# main.net
KiCad netlist of a schematic drawn in EAGLE
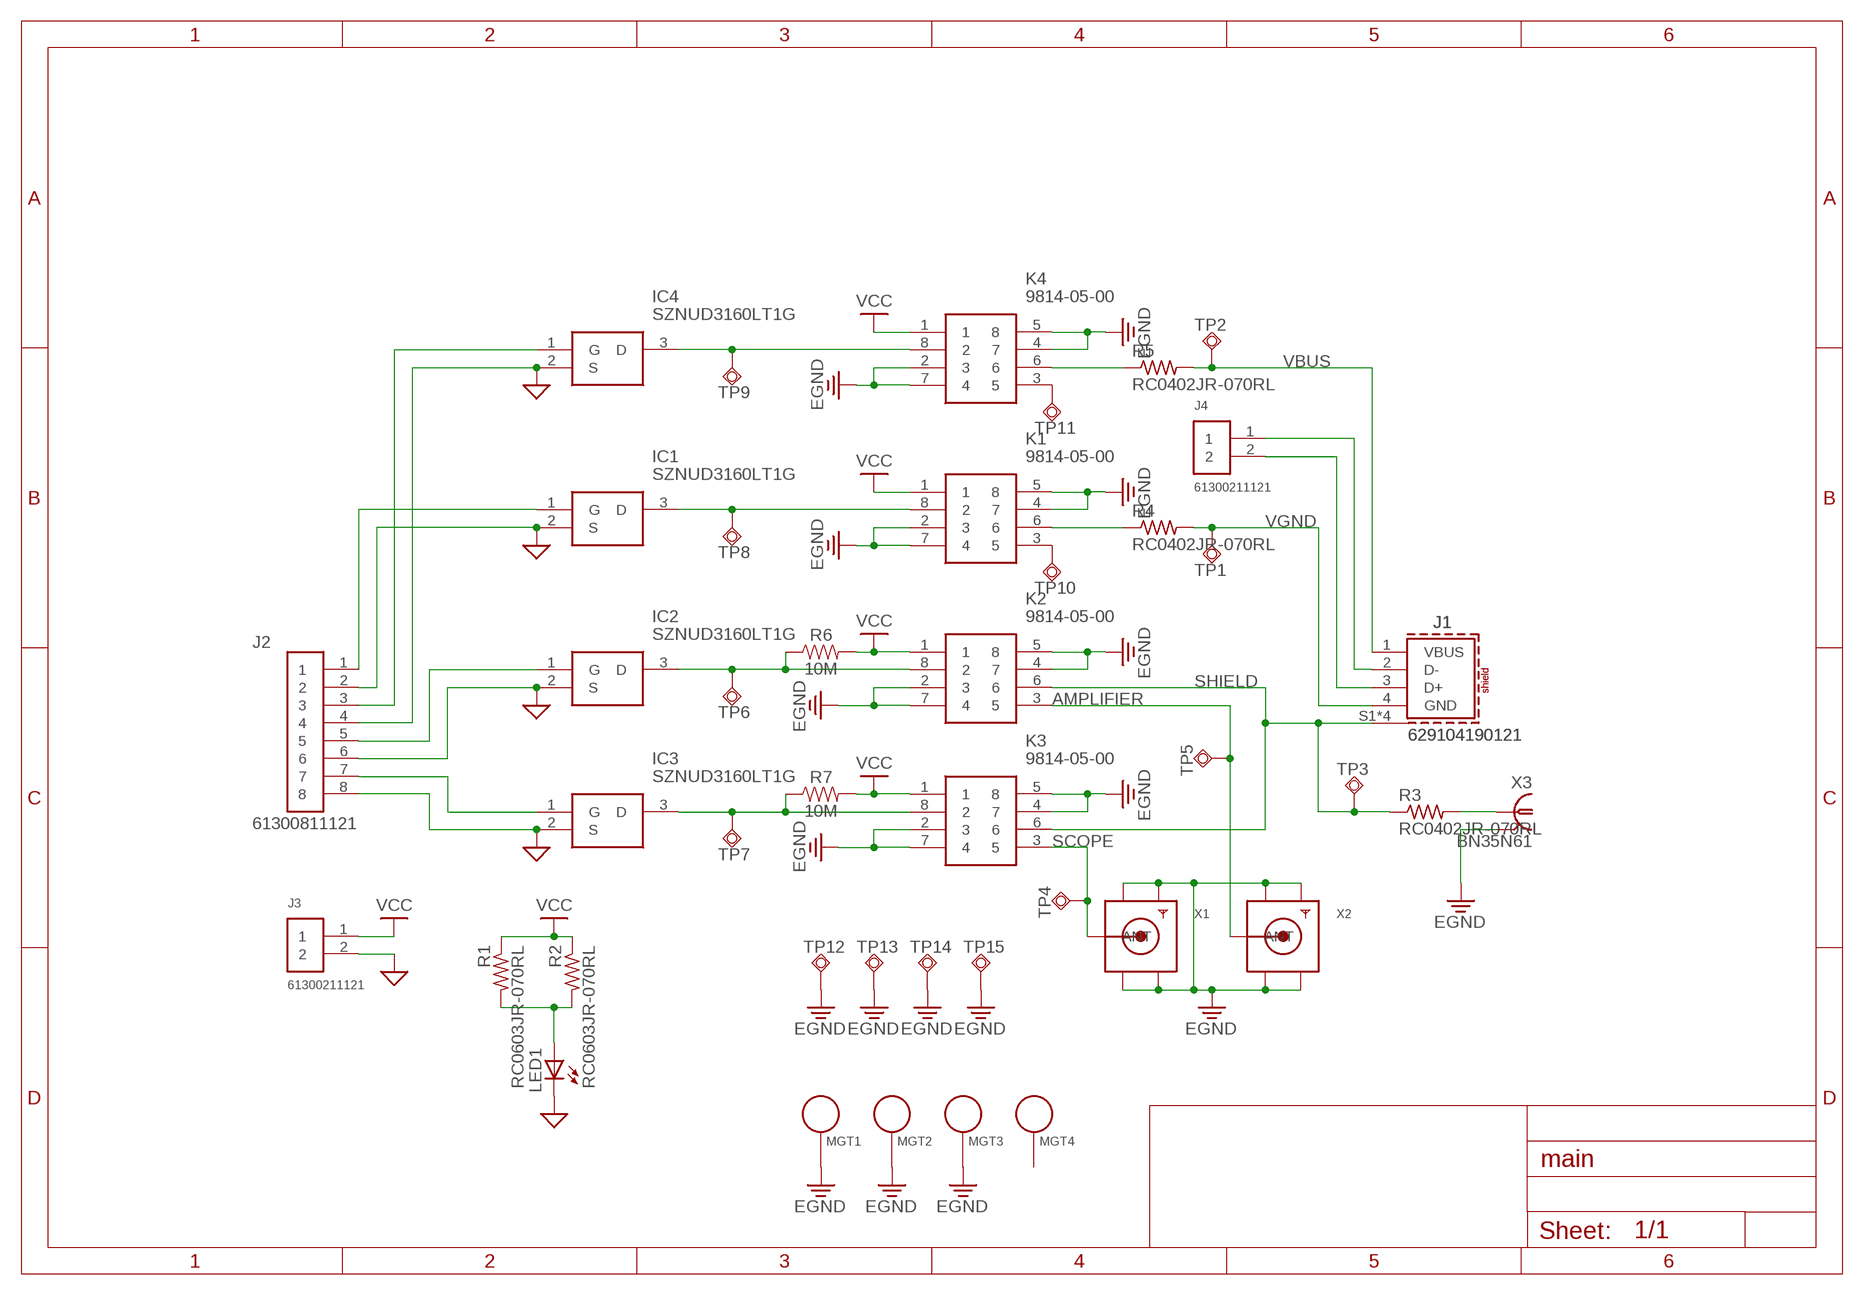
[diagram p0: schematic, sheet 1]

(export (version "E")
  (design (tool "Eeschema 10.0.6"))
  (components
    (comp (ref "IC1")
      (value "SZNUD3160LT1G")
      (footprint "eagle-import:SOT96P237X111-3N")
      (fields (field (name "MOUSER_PART_NUMBER") "863-SZNUD3160LT1G"))
      (libsource (lib "eagle-import") (part "SZNUD3160LT1G"))
    )
    (comp (ref "IC2")
      (value "SZNUD3160LT1G")
      (footprint "eagle-import:SOT96P237X111-3N")
      (fields (field (name "MOUSER_PART_NUMBER") "863-SZNUD3160LT1G"))
      (libsource (lib "eagle-import") (part "SZNUD3160LT1G"))
    )
    (comp (ref "IC3")
      (value "SZNUD3160LT1G")
      (footprint "eagle-import:SOT96P237X111-3N")
      (fields (field (name "MOUSER_PART_NUMBER") "863-SZNUD3160LT1G"))
      (libsource (lib "eagle-import") (part "SZNUD3160LT1G"))
    )
    (comp (ref "IC4")
      (value "SZNUD3160LT1G")
      (footprint "eagle-import:SOT96P237X111-3N")
      (fields (field (name "MOUSER_PART_NUMBER") "863-SZNUD3160LT1G"))
      (libsource (lib "eagle-import") (part "SZNUD3160LT1G"))
    )
    (comp (ref "J1")
      (value "629104190121")
      (footprint "eagle-import:629104190121")
      (libsource (lib "eagle-import") (part "629104190121"))
    )
    (comp (ref "J2")
      (value "61300811121")
      (footprint "eagle-import:61300811121")
      (fields
        (field (name "DIGI_KEY_PART_NUMBER") "732-5321-ND")
        (field (name "MANUFACTURER") "Wurth Electronics Inc.")
        (field (name "CREATED_BY") "PCBLayout.com")
      )
      (libsource (lib "eagle-import") (part "61300811121"))
    )
    (comp (ref "J3")
      (value "61300211121")
      (footprint "eagle-import:61300211121")
      (fields
        (field (name "DIGI_KEY_PART_NUMBER") "732-5315-ND")
        (field (name "MANUFACTURER") "Wurth Electronics Inc.")
        (field (name "CREATED_BY") "PCBLayout.com")
      )
      (libsource (lib "eagle-import") (part "61300211121"))
    )
    (comp (ref "J4")
      (value "61300211121")
      (footprint "eagle-import:61300211121")
      (fields
        (field (name "DIGI_KEY_PART_NUMBER") "732-5315-ND")
        (field (name "MANUFACTURER") "Wurth Electronics Inc.")
        (field (name "CREATED_BY") "PCBLayout.com")
      )
      (libsource (lib "eagle-import") (part "61300211121"))
    )
    (comp (ref "K1")
      (value "9814-05-00")
      (footprint "eagle-import:SOP102P1295X457-8N")
      (fields (field (name "MOUSER_PART_NUMBER") "816-9814-05-00"))
      (libsource (lib "eagle-import") (part "9814-05-00"))
    )
    (comp (ref "K2")
      (value "9814-05-00")
      (footprint "eagle-import:SOP102P1295X457-8N")
      (fields (field (name "MOUSER_PART_NUMBER") "816-9814-05-00"))
      (libsource (lib "eagle-import") (part "9814-05-00"))
    )
    (comp (ref "K3")
      (value "9814-05-00")
      (footprint "eagle-import:SOP102P1295X457-8N")
      (fields (field (name "MOUSER_PART_NUMBER") "816-9814-05-00"))
      (libsource (lib "eagle-import") (part "9814-05-00"))
    )
    (comp (ref "K4")
      (value "9814-05-00")
      (footprint "eagle-import:SOP102P1295X457-8N")
      (fields (field (name "MOUSER_PART_NUMBER") "816-9814-05-00"))
      (libsource (lib "eagle-import") (part "9814-05-00"))
    )
    (comp (ref "LED1")
      (value "LEDCHIPLED_0603")
      (footprint "eagle-import:CHIPLED_0603")
      (libsource (lib "eagle-import") (part "LEDCHIPLED_0603"))
    )
    (comp (ref "MGT1")
      (value "BEAGLEBONEBLACK_MOUNTING_HOLE")
      (footprint "eagle-import:BEAGLEBONEBLACK_MOUNTING_HOLE")
      (libsource (lib "eagle-import") (part "BEAGLEBONEBLACK_MOUNTING_HOLE"))
    )
    (comp (ref "MGT2")
      (value "BEAGLEBONEBLACK_MOUNTING_HOLE")
      (footprint "eagle-import:BEAGLEBONEBLACK_MOUNTING_HOLE")
      (libsource (lib "eagle-import") (part "BEAGLEBONEBLACK_MOUNTING_HOLE"))
    )
    (comp (ref "MGT3")
      (value "BEAGLEBONEBLACK_MOUNTING_HOLE")
      (footprint "eagle-import:BEAGLEBONEBLACK_MOUNTING_HOLE")
      (libsource (lib "eagle-import") (part "BEAGLEBONEBLACK_MOUNTING_HOLE"))
    )
    (comp (ref "MGT4")
      (value "BEAGLEBONEBLACK_MOUNTING_HOLE")
      (footprint "eagle-import:BEAGLEBONEBLACK_MOUNTING_HOLE")
      (libsource (lib "eagle-import") (part "BEAGLEBONEBLACK_MOUNTING_HOLE"))
    )
    (comp (ref "R1")
      (value "RC0603JR-070RL")
      (footprint "eagle-import:RES_0603")
      (fields
        (field (name "DIGIKEY_PART_NUMBER") "311-0.0GRTR-ND")
        (field (name "MANUFACTURER") "Yageo")
        (field (name "CREATED_BY") "PCBLayout.com")
      )
      (libsource (lib "eagle-import") (part "RC0603JR-070RL"))
    )
    (comp (ref "R2")
      (value "RC0603JR-070RL")
      (footprint "eagle-import:RES_0603")
      (fields
        (field (name "DIGIKEY_PART_NUMBER") "311-0.0GRTR-ND")
        (field (name "MANUFACTURER") "Yageo")
        (field (name "CREATED_BY") "PCBLayout.com")
      )
      (libsource (lib "eagle-import") (part "RC0603JR-070RL"))
    )
    (comp (ref "R3")
      (value "RC0402JR-070RL")
      (footprint "eagle-import:RES_0402")
      (fields
        (field (name "DIGIKEY_PART_NUMBER") "311-0.0JRTR-ND")
        (field (name "MANUFACTURER") "Yageo")
        (field (name "CREATED_BY") "PCBLayout.com")
      )
      (libsource (lib "eagle-import") (part "RC0402JR-070RL"))
    )
    (comp (ref "R4")
      (value "RC0402JR-070RL")
      (footprint "eagle-import:RES_0402")
      (fields
        (field (name "DIGIKEY_PART_NUMBER") "311-0.0JRTR-ND")
        (field (name "MANUFACTURER") "Yageo")
        (field (name "CREATED_BY") "PCBLayout.com")
      )
      (libsource (lib "eagle-import") (part "RC0402JR-070RL"))
    )
    (comp (ref "R5")
      (value "RC0402JR-070RL")
      (footprint "eagle-import:RES_0402")
      (fields
        (field (name "DIGIKEY_PART_NUMBER") "311-0.0JRTR-ND")
        (field (name "MANUFACTURER") "Yageo")
        (field (name "CREATED_BY") "PCBLayout.com")
      )
      (libsource (lib "eagle-import") (part "RC0402JR-070RL"))
    )
    (comp (ref "R6")
      (value "10M")
      (footprint "eagle-import:AXIAL-0.3")
      (libsource (lib "eagle-import") (part "10MOHM-HORIZ-1/4W-5%"))
    )
    (comp (ref "R7")
      (value "10M")
      (footprint "eagle-import:AXIAL-0.3")
      (libsource (lib "eagle-import") (part "10MOHM-HORIZ-1/4W-5%"))
    )
    (comp (ref "TP1")
      (value "TESTPAD_TPSQPAD1-13")
      (footprint "eagle-import:TESTPAD_P1-13")
      (libsource (lib "eagle-import") (part "TESTPAD_TPSQPAD1-13"))
    )
    (comp (ref "TP2")
      (value "TESTPAD_TPSQPAD1-13")
      (footprint "eagle-import:TESTPAD_P1-13")
      (libsource (lib "eagle-import") (part "TESTPAD_TPSQPAD1-13"))
    )
    (comp (ref "TP3")
      (value "TESTPAD_TPSQPAD1-13")
      (footprint "eagle-import:TESTPAD_P1-13")
      (libsource (lib "eagle-import") (part "TESTPAD_TPSQPAD1-13"))
    )
    (comp (ref "TP4")
      (value "TESTPAD_TPSQPAD1-13")
      (footprint "eagle-import:TESTPAD_P1-13")
      (libsource (lib "eagle-import") (part "TESTPAD_TPSQPAD1-13"))
    )
    (comp (ref "TP5")
      (value "TESTPAD_TPSQPAD1-13")
      (footprint "eagle-import:TESTPAD_P1-13")
      (libsource (lib "eagle-import") (part "TESTPAD_TPSQPAD1-13"))
    )
    (comp (ref "TP6")
      (value "TESTPAD_TPSQTP07SQ")
      (footprint "eagle-import:TESTPAD_TP07SQ")
      (libsource (lib "eagle-import") (part "TESTPAD_TPSQTP07SQ"))
    )
    (comp (ref "TP7")
      (value "TESTPAD_TPSQTP07SQ")
      (footprint "eagle-import:TESTPAD_TP07SQ")
      (libsource (lib "eagle-import") (part "TESTPAD_TPSQTP07SQ"))
    )
    (comp (ref "TP8")
      (value "TESTPAD_TPSQTP07SQ")
      (footprint "eagle-import:TESTPAD_TP07SQ")
      (libsource (lib "eagle-import") (part "TESTPAD_TPSQTP07SQ"))
    )
    (comp (ref "TP9")
      (value "TESTPAD_TPSQTP07SQ")
      (footprint "eagle-import:TESTPAD_TP07SQ")
      (libsource (lib "eagle-import") (part "TESTPAD_TPSQTP07SQ"))
    )
    (comp (ref "TP10")
      (value "TESTPAD_TPSQPAD1-13")
      (footprint "eagle-import:TESTPAD_P1-13")
      (libsource (lib "eagle-import") (part "TESTPAD_TPSQPAD1-13"))
    )
    (comp (ref "TP11")
      (value "TESTPAD_TPSQPAD1-13")
      (footprint "eagle-import:TESTPAD_P1-13")
      (libsource (lib "eagle-import") (part "TESTPAD_TPSQPAD1-13"))
    )
    (comp (ref "TP12")
      (value "TESTPAD_TPSQPAD1-13")
      (footprint "eagle-import:TESTPAD_P1-13")
      (libsource (lib "eagle-import") (part "TESTPAD_TPSQPAD1-13"))
    )
    (comp (ref "TP13")
      (value "TESTPAD_TPSQPAD1-13")
      (footprint "eagle-import:TESTPAD_P1-13")
      (libsource (lib "eagle-import") (part "TESTPAD_TPSQPAD1-13"))
    )
    (comp (ref "TP14")
      (value "TESTPAD_TPSQPAD1-13")
      (footprint "eagle-import:TESTPAD_P1-13")
      (libsource (lib "eagle-import") (part "TESTPAD_TPSQPAD1-13"))
    )
    (comp (ref "TP15")
      (value "TESTPAD_TPSQPAD1-13")
      (footprint "eagle-import:TESTPAD_P1-13")
      (libsource (lib "eagle-import") (part "TESTPAD_TPSQPAD1-13"))
    )
    (comp (ref "X1")
      (value "SMACONNECTOR_EDGE")
      (footprint "eagle-import:SMA_EDGELAUNCH")
      (libsource (lib "eagle-import") (part "SMACONNECTOR_EDGE"))
    )
    (comp (ref "X2")
      (value "SMACONNECTOR_EDGE")
      (footprint "eagle-import:SMA_EDGELAUNCH")
      (libsource (lib "eagle-import") (part "SMACONNECTOR_EDGE"))
    )
    (comp (ref "X3")
      (value "BN35N61")
      (footprint "eagle-import:B35N61")
      (libsource (lib "eagle-import") (part "BN35N61"))
    )
  )
  (nets
    (net (code "1") (name "/AMPLIFIER") (class "Default")
      (node (ref "K2") (pin "3") (pinfunction "5_3") (pintype "bidirectional"))
      (node (ref "TP5") (pin "TP") (pinfunction "TP_TP") (pintype "input"))
      (node (ref "X2") (pin "P") (pinfunction "ANT_P") (pintype "bidirectional"))
    )
    (net (code "2") (name "/SCOPE") (class "Default")
      (node (ref "K3") (pin "3") (pinfunction "5_3") (pintype "bidirectional"))
      (node (ref "TP4") (pin "TP") (pinfunction "TP_TP") (pintype "input"))
      (node (ref "X1") (pin "P") (pinfunction "ANT_P") (pintype "bidirectional"))
    )
    (net (code "3") (name "/SHIELD") (class "Default")
      (node (ref "J1") (pin "S1") (pinfunction "SHIELD_S1") (pintype "passive"))
      (node (ref "J1") (pin "S2") (pinfunction "SHIELD_S2") (pintype "passive"))
      (node (ref "J1") (pin "S3") (pinfunction "SHIELD_S3") (pintype "passive"))
      (node (ref "J1") (pin "S4") (pinfunction "SHIELD_S4") (pintype "passive"))
      (node (ref "K2") (pin "6") (pinfunction "6_6") (pintype "bidirectional"))
      (node (ref "K3") (pin "6") (pinfunction "6_6") (pintype "bidirectional"))
      (node (ref "R3") (pin "1") (pinfunction "1_1") (pintype "passive"))
      (node (ref "TP3") (pin "TP") (pinfunction "TP_TP") (pintype "input"))
    )
    (net (code "4") (name "/VBUS") (class "Default")
      (node (ref "J1") (pin "1") (pinfunction "VBUS_1") (pintype "passive"))
      (node (ref "R5") (pin "2") (pinfunction "2_2") (pintype "passive"))
      (node (ref "TP2") (pin "TP") (pinfunction "TP_TP") (pintype "input"))
    )
    (net (code "5") (name "/VGND") (class "Default")
      (node (ref "J1") (pin "4") (pinfunction "GND_4") (pintype "passive"))
      (node (ref "R4") (pin "2") (pinfunction "2_2") (pintype "passive"))
      (node (ref "TP1") (pin "TP") (pinfunction "TP_TP") (pintype "input"))
    )
    (net (code "6") (name "EGND") (class "Default")
      (node (ref "K1") (pin "2") (pinfunction "3_2") (pintype "bidirectional"))
      (node (ref "K1") (pin "4") (pinfunction "7_4") (pintype "bidirectional"))
      (node (ref "K1") (pin "5") (pinfunction "8_5") (pintype "bidirectional"))
      (node (ref "K1") (pin "7") (pinfunction "4_7") (pintype "bidirectional"))
      (node (ref "K2") (pin "2") (pinfunction "3_2") (pintype "bidirectional"))
      (node (ref "K2") (pin "4") (pinfunction "7_4") (pintype "bidirectional"))
      (node (ref "K2") (pin "5") (pinfunction "8_5") (pintype "bidirectional"))
      (node (ref "K2") (pin "7") (pinfunction "4_7") (pintype "bidirectional"))
      (node (ref "K3") (pin "2") (pinfunction "3_2") (pintype "bidirectional"))
      (node (ref "K3") (pin "4") (pinfunction "7_4") (pintype "bidirectional"))
      (node (ref "K3") (pin "5") (pinfunction "8_5") (pintype "bidirectional"))
      (node (ref "K3") (pin "7") (pinfunction "4_7") (pintype "bidirectional"))
      (node (ref "K4") (pin "2") (pinfunction "3_2") (pintype "bidirectional"))
      (node (ref "K4") (pin "4") (pinfunction "7_4") (pintype "bidirectional"))
      (node (ref "K4") (pin "5") (pinfunction "8_5") (pintype "bidirectional"))
      (node (ref "K4") (pin "7") (pinfunction "4_7") (pintype "bidirectional"))
      (node (ref "MGT1") (pin "P$1") (pinfunction "P$1_P$1") (pintype "bidirectional"))
      (node (ref "MGT2") (pin "P$1") (pinfunction "P$1_P$1") (pintype "bidirectional"))
      (node (ref "MGT3") (pin "P$1") (pinfunction "P$1_P$1") (pintype "bidirectional"))
      (node (ref "TP12") (pin "TP") (pinfunction "TP_TP") (pintype "input"))
      (node (ref "TP13") (pin "TP") (pinfunction "TP_TP") (pintype "input"))
      (node (ref "TP14") (pin "TP") (pinfunction "TP_TP") (pintype "input"))
      (node (ref "TP15") (pin "TP") (pinfunction "TP_TP") (pintype "input"))
      (node (ref "X1") (pin "GND@1") (pinfunction "GND4_GND@1") (pintype "power_in"))
      (node (ref "X1") (pin "GND@2") (pinfunction "GND3_GND@2") (pintype "power_in"))
      (node (ref "X1") (pin "GND@3") (pinfunction "GND2_GND@3") (pintype "power_in"))
      (node (ref "X1") (pin "GND@4") (pinfunction "GND1_GND@4") (pintype "power_in"))
      (node (ref "X2") (pin "GND@1") (pinfunction "GND4_GND@1") (pintype "power_in"))
      (node (ref "X2") (pin "GND@2") (pinfunction "GND3_GND@2") (pintype "power_in"))
      (node (ref "X2") (pin "GND@3") (pinfunction "GND2_GND@3") (pintype "power_in"))
      (node (ref "X2") (pin "GND@4") (pinfunction "GND1_GND@4") (pintype "power_in"))
      (node (ref "X3") (pin "2") (pinfunction "2_2") (pintype "passive"))
      (node (ref "X3") (pin "3") (pinfunction "2_3") (pintype "passive"))
      (node (ref "X3") (pin "4") (pinfunction "2_4") (pintype "passive"))
      (node (ref "X3") (pin "5") (pinfunction "2_5") (pintype "passive"))
    )
    (net (code "7") (name "Net-(IC1-D)") (class "Default")
      (node (ref "IC1") (pin "3") (pinfunction "D_3") (pintype "bidirectional"))
      (node (ref "K1") (pin "8") (pinfunction "2_8") (pintype "bidirectional"))
      (node (ref "TP8") (pin "TP") (pinfunction "TP_TP") (pintype "input"))
    )
    (net (code "8") (name "Net-(IC1-G)") (class "Default")
      (node (ref "IC1") (pin "1") (pinfunction "G_1") (pintype "bidirectional"))
      (node (ref "J2") (pin "1") (pinfunction "1_1") (pintype "passive"))
    )
    (net (code "9") (name "Net-(IC2-D)") (class "Default")
      (node (ref "IC2") (pin "3") (pinfunction "D_3") (pintype "bidirectional"))
      (node (ref "K2") (pin "8") (pinfunction "2_8") (pintype "bidirectional"))
      (node (ref "R6") (pin "P$1") (pinfunction "1_P$1") (pintype "passive"))
      (node (ref "TP6") (pin "TP") (pinfunction "TP_TP") (pintype "input"))
    )
    (net (code "10") (name "Net-(IC2-G)") (class "Default")
      (node (ref "IC2") (pin "1") (pinfunction "G_1") (pintype "bidirectional"))
      (node (ref "J2") (pin "5") (pinfunction "5_5") (pintype "passive"))
    )
    (net (code "11") (name "Net-(IC3-D)") (class "Default")
      (node (ref "IC3") (pin "3") (pinfunction "D_3") (pintype "bidirectional"))
      (node (ref "K3") (pin "8") (pinfunction "2_8") (pintype "bidirectional"))
      (node (ref "R7") (pin "P$1") (pinfunction "1_P$1") (pintype "passive"))
      (node (ref "TP7") (pin "TP") (pinfunction "TP_TP") (pintype "input"))
    )
    (net (code "12") (name "Net-(IC3-G)") (class "Default")
      (node (ref "IC3") (pin "1") (pinfunction "G_1") (pintype "bidirectional"))
      (node (ref "J2") (pin "7") (pinfunction "7_7") (pintype "passive"))
    )
    (net (code "13") (name "Net-(IC4-D)") (class "Default")
      (node (ref "IC4") (pin "3") (pinfunction "D_3") (pintype "bidirectional"))
      (node (ref "K4") (pin "8") (pinfunction "2_8") (pintype "bidirectional"))
      (node (ref "TP9") (pin "TP") (pinfunction "TP_TP") (pintype "input"))
    )
    (net (code "14") (name "Net-(IC4-G)") (class "Default")
      (node (ref "IC4") (pin "1") (pinfunction "G_1") (pintype "bidirectional"))
      (node (ref "J2") (pin "3") (pinfunction "3_3") (pintype "passive"))
    )
    (net (code "15") (name "Net-(J1-D+)") (class "Default")
      (node (ref "J1") (pin "3") (pinfunction "D+_3") (pintype "passive"))
      (node (ref "J4") (pin "2") (pinfunction "2_2") (pintype "passive"))
    )
    (net (code "16") (name "Net-(J1-D-)") (class "Default")
      (node (ref "J1") (pin "2") (pinfunction "D-_2") (pintype "passive"))
      (node (ref "J4") (pin "1") (pinfunction "1_1") (pintype "passive"))
    )
    (net (code "17") (name "Net-(K1-5)") (class "Default")
      (node (ref "K1") (pin "3") (pinfunction "5_3") (pintype "bidirectional"))
      (node (ref "TP10") (pin "TP") (pinfunction "TP_TP") (pintype "input"))
    )
    (net (code "18") (name "Net-(K1-Pad6)") (class "Default")
      (node (ref "K1") (pin "6") (pinfunction "6_6") (pintype "bidirectional"))
      (node (ref "R4") (pin "1") (pinfunction "1_1") (pintype "passive"))
    )
    (net (code "19") (name "Net-(K4-5)") (class "Default")
      (node (ref "K4") (pin "3") (pinfunction "5_3") (pintype "bidirectional"))
      (node (ref "TP11") (pin "TP") (pinfunction "TP_TP") (pintype "input"))
    )
    (net (code "20") (name "Net-(K4-Pad6)") (class "Default")
      (node (ref "K4") (pin "6") (pinfunction "6_6") (pintype "bidirectional"))
      (node (ref "R5") (pin "1") (pinfunction "1_1") (pintype "passive"))
    )
    (net (code "21") (name "Net-(LED1-PadA)") (class "Default")
      (node (ref "LED1") (pin "A") (pinfunction "A_A") (pintype "passive"))
      (node (ref "R1") (pin "2") (pinfunction "2_2") (pintype "passive"))
      (node (ref "R2") (pin "2") (pinfunction "2_2") (pintype "passive"))
    )
    (net (code "22") (name "Net-(R3-Pad2)") (class "Default")
      (node (ref "R3") (pin "2") (pinfunction "2_2") (pintype "passive"))
      (node (ref "X3") (pin "1") (pinfunction "1_1") (pintype "passive"))
    )
    (net (code "23") (name "SUP") (class "Default")
      (node (ref "IC1") (pin "2") (pinfunction "S_2") (pintype "bidirectional"))
      (node (ref "IC2") (pin "2") (pinfunction "S_2") (pintype "bidirectional"))
      (node (ref "IC3") (pin "2") (pinfunction "S_2") (pintype "bidirectional"))
      (node (ref "IC4") (pin "2") (pinfunction "S_2") (pintype "bidirectional"))
      (node (ref "J2") (pin "2") (pinfunction "2_2") (pintype "passive"))
      (node (ref "J2") (pin "4") (pinfunction "4_4") (pintype "passive"))
      (node (ref "J2") (pin "6") (pinfunction "6_6") (pintype "passive"))
      (node (ref "J2") (pin "8") (pinfunction "8_8") (pintype "passive"))
      (node (ref "J3") (pin "2") (pinfunction "2_2") (pintype "passive"))
      (node (ref "LED1") (pin "C") (pinfunction "C_C") (pintype "passive"))
    )
    (net (code "24") (name "VCC") (class "Default")
      (node (ref "J3") (pin "1") (pinfunction "1_1") (pintype "passive"))
      (node (ref "K1") (pin "1") (pinfunction "1_1") (pintype "bidirectional"))
      (node (ref "K2") (pin "1") (pinfunction "1_1") (pintype "bidirectional"))
      (node (ref "K3") (pin "1") (pinfunction "1_1") (pintype "bidirectional"))
      (node (ref "K4") (pin "1") (pinfunction "1_1") (pintype "bidirectional"))
      (node (ref "R1") (pin "1") (pinfunction "1_1") (pintype "passive"))
      (node (ref "R2") (pin "1") (pinfunction "1_1") (pintype "passive"))
      (node (ref "R6") (pin "P$2") (pinfunction "2_P$2") (pintype "passive"))
      (node (ref "R7") (pin "P$2") (pinfunction "2_P$2") (pintype "passive"))
    )
    (net (code "25") (name "unconnected-(MGT4-PadP$1)") (class "Default")
      (node (ref "MGT4") (pin "P$1") (pinfunction "P$1_P$1") (pintype "bidirectional"))
    )
  )
)
